# AmpSSM2019_230300.net
KiCad netlist of a schematic drawn in EAGLE
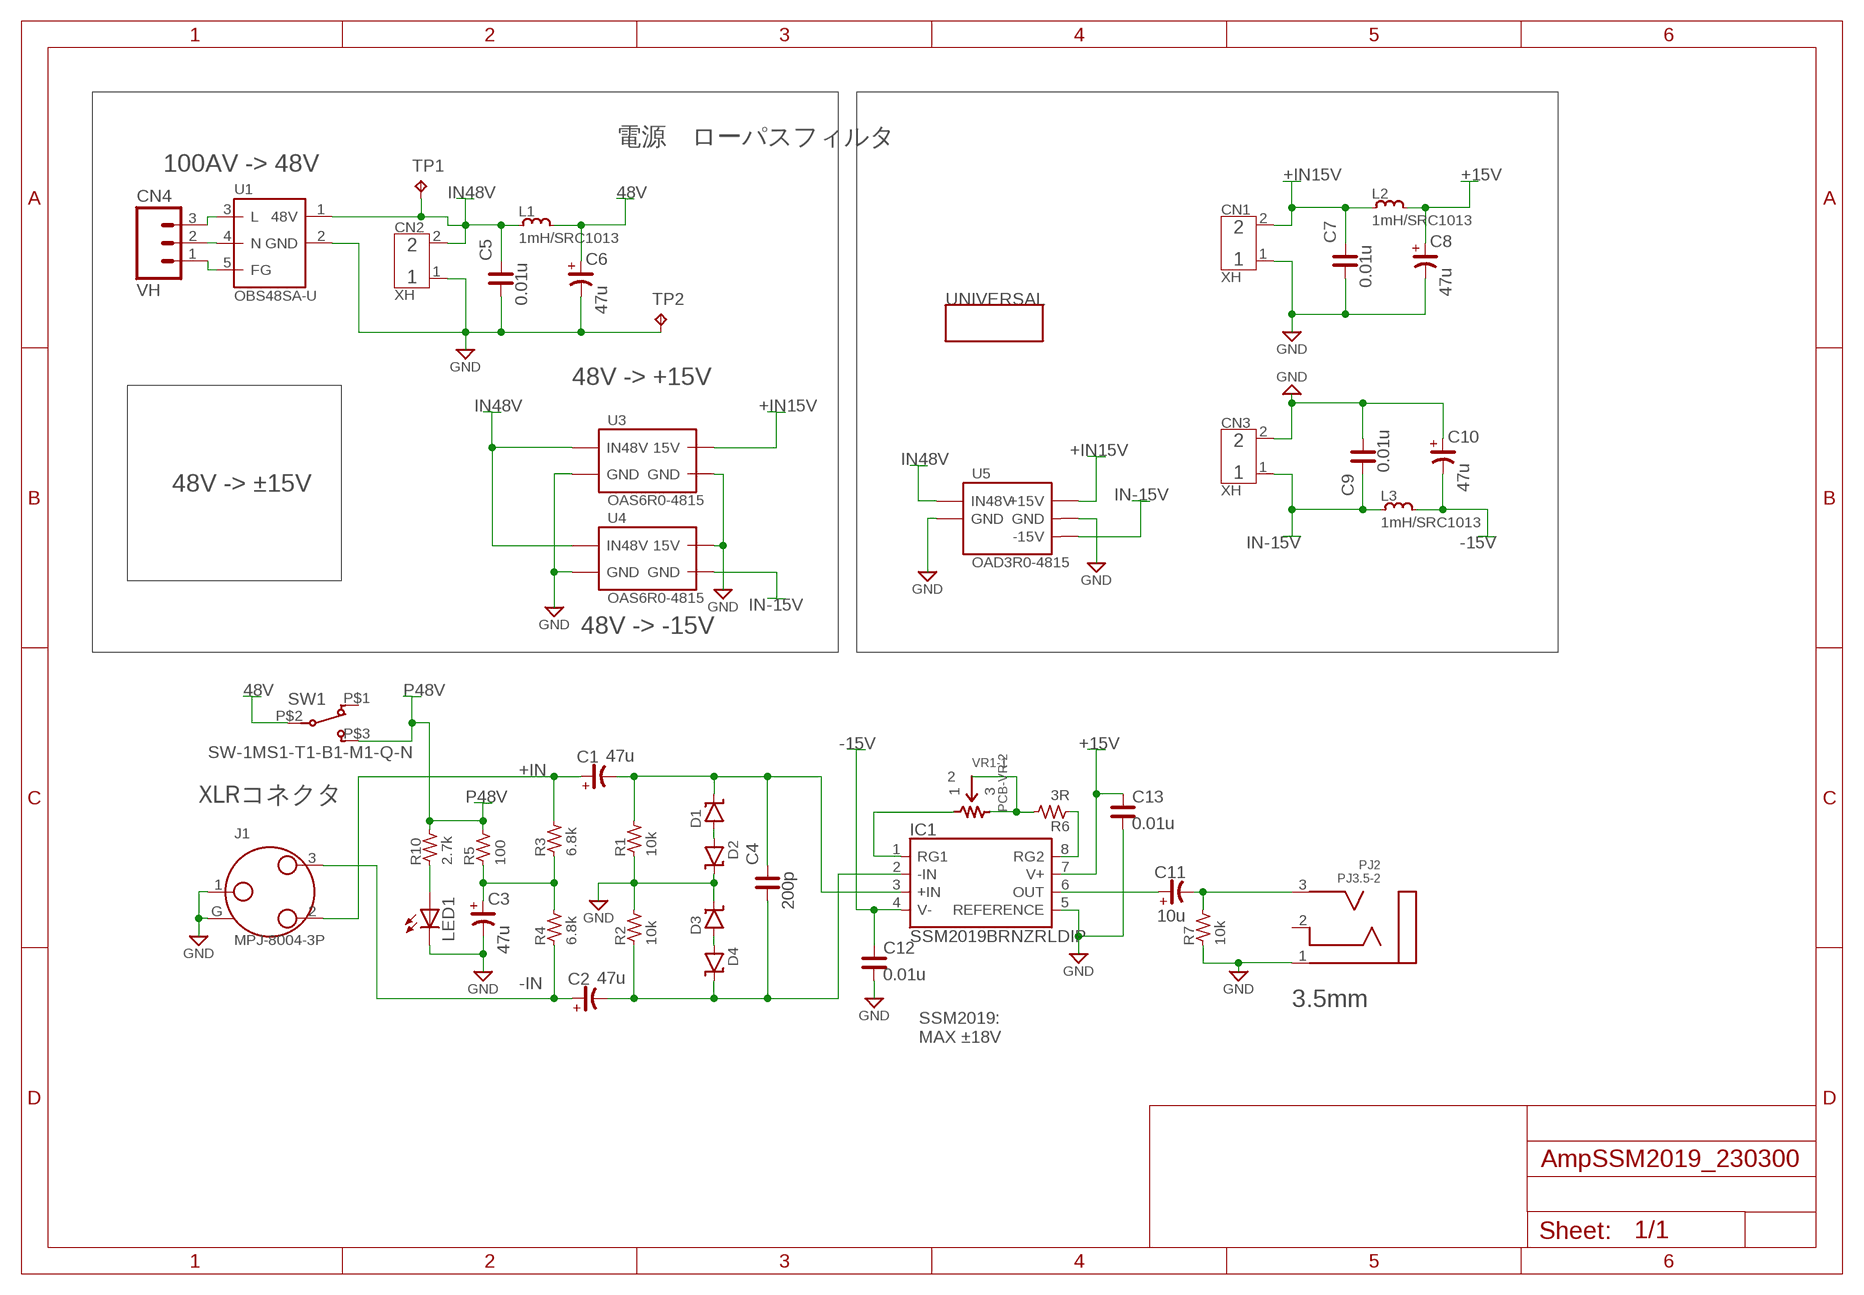
[diagram p0: schematic, sheet 1]

(export (version "E")
  (design (tool "Eeschema 10.0.6"))
  (components
    (comp (ref "C1")
      (value "47u")
      (footprint "eagle-import:CE-025X065")
      (libsource (lib "eagle-import") (part "CP_C025X065"))
    )
    (comp (ref "C2")
      (value "47u")
      (footprint "eagle-import:CE-025X065")
      (libsource (lib "eagle-import") (part "CP_C025X065"))
    )
    (comp (ref "C3")
      (value "47u")
      (footprint "eagle-import:CE-025X065")
      (libsource (lib "eagle-import") (part "CP_C025X065"))
    )
    (comp (ref "C4")
      (value "200p")
      (footprint "eagle-import:C0603")
      (libsource (lib "eagle-import") (part "C_0603"))
    )
    (comp (ref "C5")
      (value "0.01u")
      (footprint "eagle-import:C0603")
      (libsource (lib "eagle-import") (part "C_0603"))
    )
    (comp (ref "C6")
      (value "47u")
      (footprint "eagle-import:CE-025X065")
      (libsource (lib "eagle-import") (part "CP_C025X065"))
    )
    (comp (ref "C7")
      (value "0.01u")
      (footprint "eagle-import:C0603")
      (libsource (lib "eagle-import") (part "C_0603"))
    )
    (comp (ref "C8")
      (value "47u")
      (footprint "eagle-import:CE-025X065")
      (libsource (lib "eagle-import") (part "CP_C025X065"))
    )
    (comp (ref "C9")
      (value "0.01u")
      (footprint "eagle-import:C0603")
      (libsource (lib "eagle-import") (part "C_0603"))
    )
    (comp (ref "C10")
      (value "47u")
      (footprint "eagle-import:CE-025X065")
      (libsource (lib "eagle-import") (part "CP_C025X065"))
    )
    (comp (ref "C11")
      (value "10u")
      (footprint "eagle-import:CE-025X065")
      (libsource (lib "eagle-import") (part "CP_C025X065"))
    )
    (comp (ref "C12")
      (value "0.01u")
      (footprint "eagle-import:C0603")
      (libsource (lib "eagle-import") (part "C_0603"))
    )
    (comp (ref "C13")
      (value "0.01u")
      (footprint "eagle-import:C0603")
      (libsource (lib "eagle-import") (part "C_0603"))
    )
    (comp (ref "CN1")
      (value "XH")
      (footprint "eagle-import:B2B-XH-A")
      (libsource (lib "eagle-import") (part "CN-B2B-XH-A"))
    )
    (comp (ref "CN2")
      (value "XH")
      (footprint "eagle-import:B2B-XH-A")
      (libsource (lib "eagle-import") (part "CN-B2B-XH-A"))
    )
    (comp (ref "CN3")
      (value "XH")
      (footprint "eagle-import:B2B-XH-A")
      (libsource (lib "eagle-import") (part "CN-B2B-XH-A"))
    )
    (comp (ref "CN4")
      (value "VH")
      (footprint "eagle-import:VH3")
      (libsource (lib "eagle-import") (part "M03VH"))
    )
    (comp (ref "D1")
      (value "ZD323")
      (footprint "eagle-import:SOD-323")
      (libsource (lib "eagle-import") (part "ZD323"))
    )
    (comp (ref "D2")
      (value "ZD323")
      (footprint "eagle-import:SOD-323")
      (libsource (lib "eagle-import") (part "ZD323"))
    )
    (comp (ref "D3")
      (value "ZD323")
      (footprint "eagle-import:SOD-323")
      (libsource (lib "eagle-import") (part "ZD323"))
    )
    (comp (ref "D4")
      (value "ZD323")
      (footprint "eagle-import:SOD-323")
      (libsource (lib "eagle-import") (part "ZD323"))
    )
    (comp (ref "IC1")
      (value "SSM2019BRNZRLDIP")
      (footprint "eagle-import:DIL08")
      (libsource (lib "eagle-import") (part "SSM2019BRNZRLDIP"))
    )
    (comp (ref "J1")
      (value "MPJ-8004-3P")
      (footprint "eagle-import:MPJ-8004-3P")
      (libsource (lib "eagle-import") (part "MPJ-8004-3P"))
    )
    (comp (ref "L1")
      (value "1mH/SRC1013")
      (footprint "eagle-import:L13X15")
      (libsource (lib "eagle-import") (part "L_13X15"))
    )
    (comp (ref "L2")
      (value "1mH/SRC1013")
      (footprint "eagle-import:L13X15")
      (libsource (lib "eagle-import") (part "L_13X15"))
    )
    (comp (ref "L3")
      (value "1mH/SRC1013")
      (footprint "eagle-import:L13X15")
      (libsource (lib "eagle-import") (part "L_13X15"))
    )
    (comp (ref "LED1")
      (value "LED3MM")
      (footprint "eagle-import:LED3MM")
      (libsource (lib "eagle-import") (part "LED3MM"))
    )
    (comp (ref "PJ2")
      (value "PJ3.5-2")
      (footprint "eagle-import:PJ3.5-2")
      (libsource (lib "eagle-import") (part "PJ3.5-2"))
    )
    (comp (ref "R1")
      (value "10k")
      (footprint "eagle-import:R0603")
      (libsource (lib "eagle-import") (part "R_0603"))
    )
    (comp (ref "R2")
      (value "10k")
      (footprint "eagle-import:R0603")
      (libsource (lib "eagle-import") (part "R_0603"))
    )
    (comp (ref "R3")
      (value "6.8k")
      (footprint "eagle-import:R0603")
      (libsource (lib "eagle-import") (part "R_0603"))
    )
    (comp (ref "R4")
      (value "6.8k")
      (footprint "eagle-import:R0603")
      (libsource (lib "eagle-import") (part "R_0603"))
    )
    (comp (ref "R5")
      (value "100")
      (footprint "eagle-import:R0603")
      (libsource (lib "eagle-import") (part "R_0603"))
    )
    (comp (ref "R6")
      (value "3R")
      (footprint "eagle-import:R0603")
      (libsource (lib "eagle-import") (part "R_0603"))
    )
    (comp (ref "R7")
      (value "10k")
      (footprint "eagle-import:R0603")
      (libsource (lib "eagle-import") (part "R_0603"))
    )
    (comp (ref "R10")
      (value "2.7k")
      (footprint "eagle-import:R0603")
      (libsource (lib "eagle-import") (part "R_0603"))
    )
    (comp (ref "SW1")
      (value "SW-1MS1-T1-B1-M1-Q-N")
      (footprint "eagle-import:1MS1-T1-B1-M1-Q-N")
      (libsource (lib "eagle-import") (part "SW-1MS1-T1-B1-M1-Q-N"))
    )
    (comp (ref "TP1")
      (value "TPPAD1-13")
      (footprint "eagle-import:P1-13")
      (libsource (lib "eagle-import") (part "TPPAD1-13"))
    )
    (comp (ref "TP2")
      (value "TPPAD1-13")
      (footprint "eagle-import:P1-13")
      (libsource (lib "eagle-import") (part "TPPAD1-13"))
    )
    (comp (ref "U1")
      (value "OBS48SA-U")
      (footprint "eagle-import:OBS48SA-U")
      (libsource (lib "eagle-import") (part "OBS48SA-U"))
    )
    (comp (ref "U2")
      (value "UNIVERSAL10X10")
      (footprint "eagle-import:UNIVERSAL10X10")
      (libsource (lib "eagle-import") (part "UNIVERSAL10X10"))
    )
    (comp (ref "U3")
      (value "OAS6R0-4815")
      (footprint "eagle-import:OAS6R0-4815")
      (libsource (lib "eagle-import") (part "OAS6R0-4815"))
    )
    (comp (ref "U4")
      (value "OAS6R0-4815")
      (footprint "eagle-import:OAS6R0-4815")
      (libsource (lib "eagle-import") (part "OAS6R0-4815"))
    )
    (comp (ref "U5")
      (value "OAD3R0-4815")
      (footprint "eagle-import:OAD3R0-4815")
      (libsource (lib "eagle-import") (part "OAD3R0-4815"))
    )
    (comp (ref "VR1")
      (value "PCB-VR-2")
      (footprint "eagle-import:PCB-VR-2")
      (libsource (lib "eagle-import") (part "PCB-VR-2"))
    )
  )
  (nets
    (net (code "1") (name "/+15V") (class "Default")
      (node (ref "C13") (pin "2") (pinfunction "2_2") (pintype "passive"))
      (node (ref "C8") (pin "+") (pinfunction "+_+") (pintype "passive"))
      (node (ref "IC1") (pin "7") (pinfunction "V+_7") (pintype "bidirectional"))
      (node (ref "L2") (pin "2") (pinfunction "2_2") (pintype "passive"))
    )
    (net (code "2") (name "/+IN") (class "Default")
      (node (ref "C1") (pin "+") (pinfunction "+_+") (pintype "passive"))
      (node (ref "J1") (pin "2") (pinfunction "2_2") (pintype "bidirectional"))
      (node (ref "R3") (pin "2") (pinfunction "2_2") (pintype "passive"))
    )
    (net (code "3") (name "/+IN15V") (class "Default")
      (node (ref "C7") (pin "2") (pinfunction "2_2") (pintype "passive"))
      (node (ref "CN1") (pin "2") (pinfunction "2_2") (pintype "passive"))
      (node (ref "L2") (pin "1") (pinfunction "1_1") (pintype "passive"))
      (node (ref "U3") (pin "V_OUT") (pinfunction "15V_V_OUT") (pintype "bidirectional"))
      (node (ref "U5") (pin "V+_OUT") (pinfunction "+15V_V+_OUT") (pintype "bidirectional"))
    )
    (net (code "4") (name "/-15V") (class "Default")
      (node (ref "C10") (pin "-") (pinfunction "-_-") (pintype "passive"))
      (node (ref "C12") (pin "2") (pinfunction "2_2") (pintype "passive"))
      (node (ref "IC1") (pin "4") (pinfunction "V-_4") (pintype "bidirectional"))
      (node (ref "L3") (pin "2") (pinfunction "2_2") (pintype "passive"))
    )
    (net (code "5") (name "/-IN") (class "Default")
      (node (ref "C2") (pin "+") (pinfunction "+_+") (pintype "passive"))
      (node (ref "J1") (pin "3") (pinfunction "3_3") (pintype "bidirectional"))
      (node (ref "R4") (pin "1") (pinfunction "1_1") (pintype "passive"))
    )
    (net (code "6") (name "/48V") (class "Default")
      (node (ref "C6") (pin "+") (pinfunction "+_+") (pintype "passive"))
      (node (ref "L1") (pin "2") (pinfunction "2_2") (pintype "passive"))
      (node (ref "SW1") (pin "P$2") (pinfunction "P_P$2") (pintype "passive"))
    )
    (net (code "7") (name "/IN-15V") (class "Default")
      (node (ref "C9") (pin "2") (pinfunction "2_2") (pintype "passive"))
      (node (ref "CN3") (pin "1") (pinfunction "1_1") (pintype "passive"))
      (node (ref "L3") (pin "1") (pinfunction "1_1") (pintype "passive"))
      (node (ref "U4") (pin "G_OUT") (pinfunction "GND_G_OUT") (pintype "bidirectional"))
      (node (ref "U5") (pin "V-_OUT") (pinfunction "-15V_V-_OUT") (pintype "bidirectional"))
    )
    (net (code "8") (name "/IN48V") (class "Default")
      (node (ref "C5") (pin "2") (pinfunction "2_2") (pintype "passive"))
      (node (ref "CN2") (pin "2") (pinfunction "2_2") (pintype "passive"))
      (node (ref "L1") (pin "1") (pinfunction "1_1") (pintype "passive"))
      (node (ref "TP1") (pin "TP") (pinfunction "TP_TP") (pintype "input"))
      (node (ref "U1") (pin "1") (pinfunction "48V_1") (pintype "bidirectional"))
      (node (ref "U3") (pin "VIN") (pinfunction "IN48V_VIN") (pintype "bidirectional"))
      (node (ref "U4") (pin "VIN") (pinfunction "IN48V_VIN") (pintype "bidirectional"))
      (node (ref "U5") (pin "VIN") (pinfunction "IN48V_VIN") (pintype "bidirectional"))
    )
    (net (code "9") (name "/P48V") (class "Default")
      (node (ref "R10") (pin "2") (pinfunction "2_2") (pintype "passive"))
      (node (ref "R5") (pin "2") (pinfunction "2_2") (pintype "passive"))
      (node (ref "SW1") (pin "P$3") (pinfunction "S_P$3") (pintype "passive"))
    )
    (net (code "10") (name "G") (class "Default")
      (node (ref "C10") (pin "+") (pinfunction "+_+") (pintype "passive"))
      (node (ref "C12") (pin "1") (pinfunction "1_1") (pintype "passive"))
      (node (ref "C13") (pin "1") (pinfunction "1_1") (pintype "passive"))
      (node (ref "C3") (pin "-") (pinfunction "-_-") (pintype "passive"))
      (node (ref "C5") (pin "1") (pinfunction "1_1") (pintype "passive"))
      (node (ref "C6") (pin "-") (pinfunction "-_-") (pintype "passive"))
      (node (ref "C7") (pin "1") (pinfunction "1_1") (pintype "passive"))
      (node (ref "C8") (pin "-") (pinfunction "-_-") (pintype "passive"))
      (node (ref "C9") (pin "1") (pinfunction "1_1") (pintype "passive"))
      (node (ref "CN1") (pin "1") (pinfunction "1_1") (pintype "passive"))
      (node (ref "CN2") (pin "1") (pinfunction "1_1") (pintype "passive"))
      (node (ref "CN3") (pin "2") (pinfunction "2_2") (pintype "passive"))
      (node (ref "D2") (pin "K") (pinfunction "C_K") (pintype "passive"))
      (node (ref "D3") (pin "K") (pinfunction "C_K") (pintype "passive"))
      (node (ref "IC1") (pin "5") (pinfunction "REFERENCE_5") (pintype "bidirectional"))
      (node (ref "J1") (pin "1") (pinfunction "1_1") (pintype "bidirectional"))
      (node (ref "J1") (pin "G") (pinfunction "G_G") (pintype "bidirectional"))
      (node (ref "LED1") (pin "K") (pinfunction "C_K") (pintype "passive"))
      (node (ref "PJ2") (pin "1") (pinfunction "S_1") (pintype "passive"))
      (node (ref "R1") (pin "1") (pinfunction "1_1") (pintype "passive"))
      (node (ref "R2") (pin "2") (pinfunction "2_2") (pintype "passive"))
      (node (ref "R7") (pin "1") (pinfunction "1_1") (pintype "passive"))
      (node (ref "TP2") (pin "TP") (pinfunction "TP_TP") (pintype "input"))
      (node (ref "U1") (pin "2") (pinfunction "GND_2") (pintype "bidirectional"))
      (node (ref "U3") (pin "G_IN") (pinfunction "GND_G_IN") (pintype "bidirectional"))
      (node (ref "U3") (pin "G_OUT") (pinfunction "GND_G_OUT") (pintype "bidirectional"))
      (node (ref "U4") (pin "G_IN") (pinfunction "GND_G_IN") (pintype "bidirectional"))
      (node (ref "U4") (pin "V_OUT") (pinfunction "15V_V_OUT") (pintype "bidirectional"))
      (node (ref "U5") (pin "G_IN") (pinfunction "GND_G_IN") (pintype "bidirectional"))
      (node (ref "U5") (pin "G_OUT") (pinfunction "GND_G_OUT") (pintype "bidirectional"))
    )
    (net (code "11") (name "Net-(C3-Pad+)") (class "Default")
      (node (ref "C3") (pin "+") (pinfunction "+_+") (pintype "passive"))
      (node (ref "R3") (pin "1") (pinfunction "1_1") (pintype "passive"))
      (node (ref "R4") (pin "2") (pinfunction "2_2") (pintype "passive"))
      (node (ref "R5") (pin "1") (pinfunction "1_1") (pintype "passive"))
    )
    (net (code "12") (name "Net-(D1-C)") (class "Default")
      (node (ref "C1") (pin "-") (pinfunction "-_-") (pintype "passive"))
      (node (ref "C4") (pin "2") (pinfunction "2_2") (pintype "passive"))
      (node (ref "D1") (pin "K") (pinfunction "C_K") (pintype "passive"))
      (node (ref "IC1") (pin "3") (pinfunction "+IN_3") (pintype "bidirectional"))
      (node (ref "R1") (pin "2") (pinfunction "2_2") (pintype "passive"))
    )
    (net (code "13") (name "Net-(D1-PadA)") (class "Default")
      (node (ref "D1") (pin "A") (pinfunction "A_A") (pintype "passive"))
      (node (ref "D2") (pin "A") (pinfunction "A_A") (pintype "passive"))
    )
    (net (code "14") (name "Net-(D3-PadA)") (class "Default")
      (node (ref "D3") (pin "A") (pinfunction "A_A") (pintype "passive"))
      (node (ref "D4") (pin "A") (pinfunction "A_A") (pintype "passive"))
    )
    (net (code "15") (name "Net-(D4-C)") (class "Default")
      (node (ref "C2") (pin "-") (pinfunction "-_-") (pintype "passive"))
      (node (ref "C4") (pin "1") (pinfunction "1_1") (pintype "passive"))
      (node (ref "D4") (pin "K") (pinfunction "C_K") (pintype "passive"))
      (node (ref "IC1") (pin "2") (pinfunction "-IN_2") (pintype "bidirectional"))
      (node (ref "R2") (pin "1") (pinfunction "1_1") (pintype "passive"))
    )
    (net (code "16") (name "Net-(IC1-OUT)") (class "Default")
      (node (ref "C11") (pin "+") (pinfunction "+_+") (pintype "passive"))
      (node (ref "IC1") (pin "6") (pinfunction "OUT_6") (pintype "bidirectional"))
    )
    (net (code "17") (name "Net-(IC1-RG1)") (class "Default")
      (node (ref "IC1") (pin "1") (pinfunction "RG1_1") (pintype "bidirectional"))
      (node (ref "VR1") (pin "3") (pinfunction "1_3") (pintype "passive"))
    )
    (net (code "18") (name "Net-(IC1-RG2)") (class "Default")
      (node (ref "IC1") (pin "8") (pinfunction "RG2_8") (pintype "bidirectional"))
      (node (ref "R6") (pin "1") (pinfunction "1_1") (pintype "passive"))
    )
    (net (code "19") (name "Net-(LED1-PadA)") (class "Default")
      (node (ref "LED1") (pin "A") (pinfunction "A_A") (pintype "passive"))
      (node (ref "R10") (pin "1") (pinfunction "1_1") (pintype "passive"))
    )
    (net (code "20") (name "Net-(PJ2-TIP)") (class "Default")
      (node (ref "C11") (pin "-") (pinfunction "-_-") (pintype "passive"))
      (node (ref "PJ2") (pin "3") (pinfunction "TIP_3") (pintype "passive"))
      (node (ref "R7") (pin "2") (pinfunction "2_2") (pintype "passive"))
    )
    (net (code "21") (name "Net-(U1-FG)") (class "Default")
      (node (ref "CN4") (pin "1") (pinfunction "1_1") (pintype "passive"))
      (node (ref "U1") (pin "5") (pinfunction "FG_5") (pintype "bidirectional"))
    )
    (net (code "22") (name "Net-(U1-L)") (class "Default")
      (node (ref "CN4") (pin "3") (pinfunction "3_3") (pintype "passive"))
      (node (ref "U1") (pin "3") (pinfunction "L_3") (pintype "bidirectional"))
    )
    (net (code "23") (name "Net-(U1-N)") (class "Default")
      (node (ref "CN4") (pin "2") (pinfunction "2_2") (pintype "passive"))
      (node (ref "U1") (pin "4") (pinfunction "N_4") (pintype "bidirectional"))
    )
    (net (code "24") (name "Net-(VR1A-3)") (class "Default")
      (node (ref "R6") (pin "2") (pinfunction "2_2") (pintype "passive"))
      (node (ref "VR1") (pin "1") (pinfunction "3_1") (pintype "passive"))
      (node (ref "VR1") (pin "2") (pinfunction "2_2") (pintype "passive"))
    )
    (net (code "25") (name "unconnected-(PJ2-RING-Pad2)") (class "Default")
      (node (ref "PJ2") (pin "2") (pinfunction "RING_2") (pintype "passive"))
    )
    (net (code "26") (name "unconnected-(SW1-O-PadP$1)") (class "Default")
      (node (ref "SW1") (pin "P$1") (pinfunction "O_P$1") (pintype "passive"))
    )
  )
)
